# turnsig2.net
KiCad netlist of a schematic drawn in Altium Designer
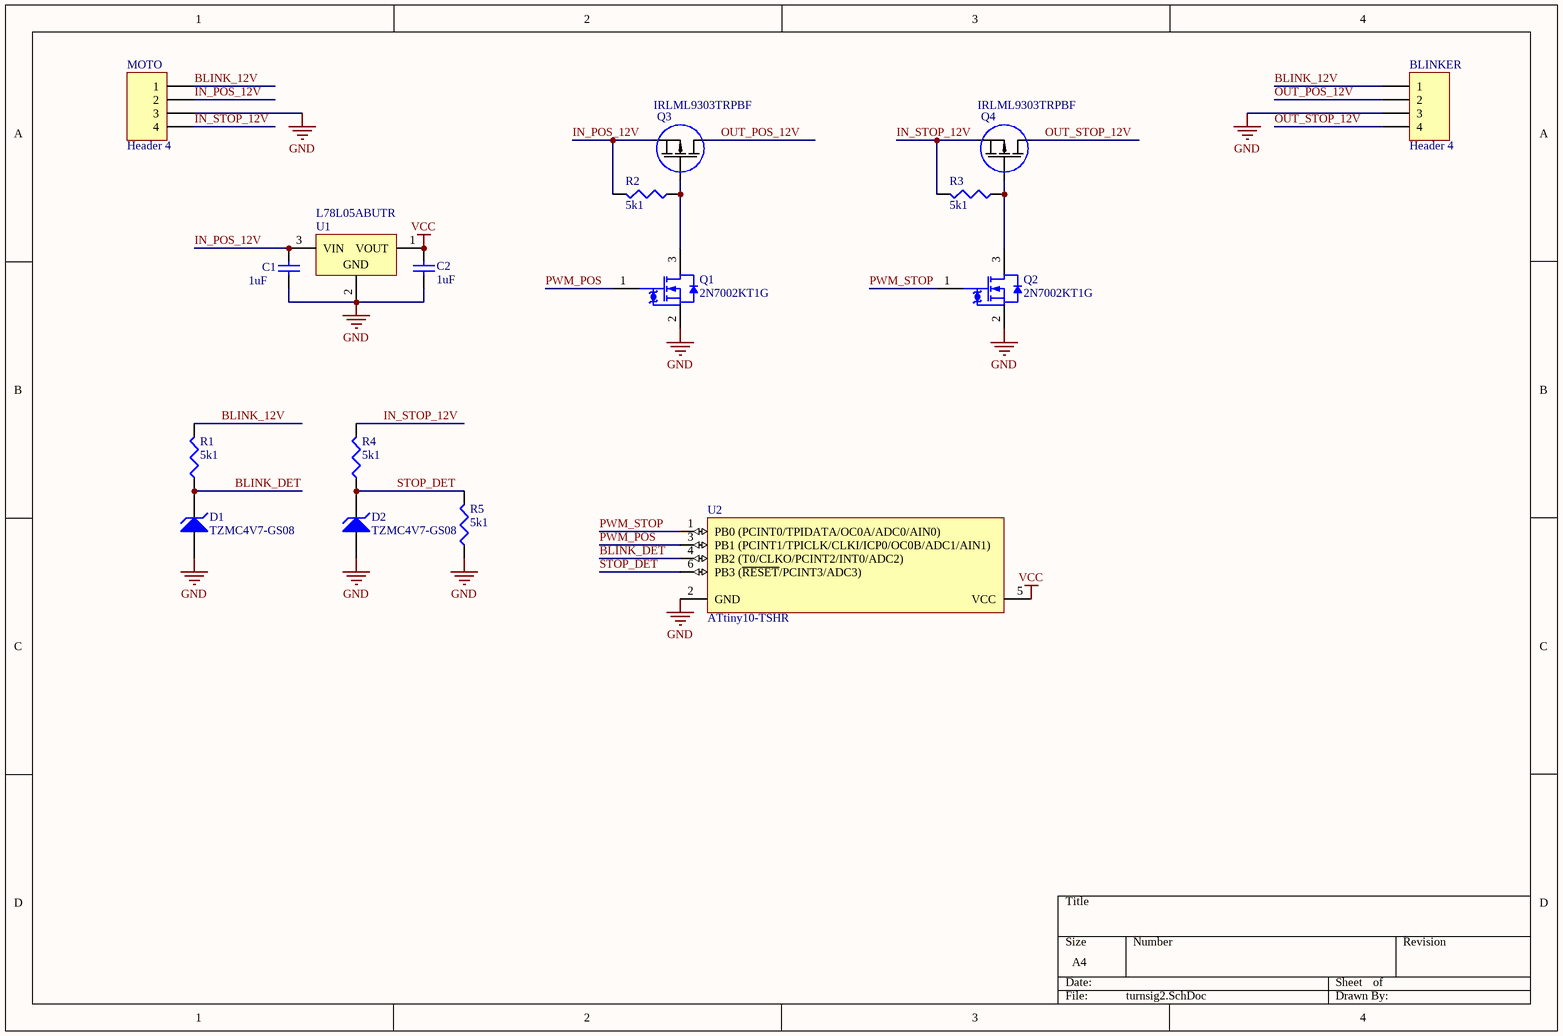
[diagram p0: turnsig2.SchDoc]

(export (version "E")
  (design (tool "Eeschema 10.0.6"))
  (components
    (comp (ref "BLINKER")
      (value "Header 4")
      (footprint "wireheader")
      (description "Header, 4-Pin")
      (fields (field (name "PUBLISHER") "Altium Limited"))
      (libsource (lib "") (part "Header 4_1"))
    )
    (comp (ref "C1")
      (value "1uF")
      (footprint "1608[0603]")
      (description "Capacitor (Semiconductor SIM Model)")
      (fields (field (name "Comment") "Cap Semi") (field (name "PUBLISHER") "Altium Limited"))
      (libsource (lib "Miscellaneous Devices") (part "Cap Semi"))
    )
    (comp (ref "C2")
      (value "1uF")
      (footprint "1608[0603]")
      (description "Capacitor (Semiconductor SIM Model)")
      (fields (field (name "Comment") "Cap Semi") (field (name "PUBLISHER") "Altium Limited"))
      (libsource (lib "Miscellaneous Devices") (part "Cap Semi"))
    )
    (comp (ref "D1")
      (value "TZMC4V7-GS08")
      (footprint "SOD-80/MLL34")
      (fields (field (name "VOLTAGE") "4V7") (field (name "PUBLISHER") "Altium Limited"))
      (libsource (lib "Miscellaneous Devices") (part "D Zener"))
    )
    (comp (ref "D2")
      (value "TZMC4V7-GS08")
      (footprint "SOD-80/MLL34")
      (fields (field (name "VOLTAGE") "4V7") (field (name "PUBLISHER") "Altium Limited"))
      (libsource (lib "Miscellaneous Devices") (part "D Zener"))
    )
    (comp (ref "MOTO")
      (value "Header 4")
      (footprint "wireheader")
      (description "Header, 4-Pin")
      (fields (field (name "PUBLISHER") "Altium Limited"))
      (libsource (lib "Miscellaneous Connectors") (part "Header 4"))
    )
    (comp (ref "Q1")
      (value "2N7002KT1G")
      (footprint "ONSC-SOT-23-3-318-08_V")
      (description "Small Signal MOSFET, 60 V, 380 mA, Single, N-Channel, 3-Pin SOT-23, Pb-Free, Tape and Reel")
      (fields (field (name "MANUFACTURER") "On Semiconductor"))
      (libsource (lib "ON Semi MOSFETs") (part "2N7002KT1G"))
    )
    (comp (ref "Q2")
      (value "2N7002KT1G")
      (footprint "ONSC-SOT-23-3-318-08_V")
      (description "Small Signal MOSFET, 60 V, 380 mA, Single, N-Channel, 3-Pin SOT-23, Pb-Free, Tape and Reel")
      (fields (field (name "MANUFACTURER") "On Semiconductor"))
      (libsource (lib "ON Semi MOSFETs") (part "2N7002KT1G"))
    )
    (comp (ref "Q3")
      (value "IRLML9303TRPBF")
      (footprint "SOT23-3N")
      (description "MOSFET-P")
      (libsource (lib "SI2323") (part "SI2323DS"))
    )
    (comp (ref "Q4")
      (value "IRLML9303TRPBF")
      (footprint "SOT23-3N")
      (description "MOSFET-P")
      (libsource (lib "SI2323") (part "SI2323DS"))
    )
    (comp (ref "R1")
      (value "5k1")
      (footprint "J1-0603")
      (description "Resistor")
      (fields (field (name "Comment") "Res3") (field (name "PUBLISHER") "Altium Limited"))
      (libsource (lib "Miscellaneous Devices") (part "Res3"))
    )
    (comp (ref "R2")
      (value "5k1")
      (footprint "J1-0603")
      (description "Resistor")
      (fields (field (name "Comment") "Res3") (field (name "PUBLISHER") "Altium Limited"))
      (libsource (lib "Miscellaneous Devices") (part "Res3"))
    )
    (comp (ref "R3")
      (value "5k1")
      (footprint "J1-0603")
      (description "Resistor")
      (fields (field (name "Comment") "Res3") (field (name "PUBLISHER") "Altium Limited"))
      (libsource (lib "Miscellaneous Devices") (part "Res3"))
    )
    (comp (ref "R4")
      (value "5k1")
      (footprint "J1-0603")
      (description "Resistor")
      (fields (field (name "Comment") "Res3") (field (name "PUBLISHER") "Altium Limited"))
      (libsource (lib "Miscellaneous Devices") (part "Res3"))
    )
    (comp (ref "R5")
      (value "5k1")
      (footprint "J1-0603")
      (description "Resistor")
      (fields (field (name "Comment") "Res3") (field (name "PUBLISHER") "Altium Limited"))
      (libsource (lib "Miscellaneous Devices") (part "Res3"))
    )
    (comp (ref "U1")
      (value "L78L05ABUTR")
      (footprint "SOT-89_N")
      (description "Positive Voltage Regulator, 5V, 4-Pin SOT-89, Tape and Reel")
      (libsource (lib "STMicroelectronics Power Management Linear Regulator") (part "L78L05ABUTR"))
    )
    (comp (ref "U2")
      (value "ATtiny10-TSHR")
      (footprint "6ST1_N")
      (fields (field (name "PUBLISHER") "Altium Limited"))
      (libsource (lib "Atmel Microcontroller 8-Bit tinyAVR") (part "ATtiny10-TSHR"))
    )
  )
  (nets
    (net (code "1") (name "/BLINK_12V") (class "Default")
      (node (ref "BLINKER") (pin "1") (pinfunction "1_1") (pintype "passive"))
      (node (ref "MOTO") (pin "1") (pinfunction "1_1") (pintype "passive"))
      (node (ref "R1") (pin "2") (pinfunction "2_2") (pintype "passive"))
    )
    (net (code "2") (name "/BLINK_DET") (class "Default")
      (node (ref "D1") (pin "2") (pinfunction "K_2") (pintype "passive"))
      (node (ref "R1") (pin "1") (pinfunction "1_1") (pintype "passive"))
      (node (ref "U2") (pin "4") (pinfunction "PB2_(T0/CLKO/PCINT2/INT0/ADC2)_4") (pintype "bidirectional"))
    )
    (net (code "3") (name "/IN_POS_12V") (class "Default")
      (node (ref "C1") (pin "1") (pinfunction "1_1") (pintype "passive"))
      (node (ref "MOTO") (pin "2") (pinfunction "2_2") (pintype "passive"))
      (node (ref "Q3") (pin "2") (pinfunction "S_2") (pintype "passive"))
      (node (ref "R2") (pin "2") (pinfunction "2_2") (pintype "passive"))
      (node (ref "U1") (pin "3") (pinfunction "VIN_3") (pintype "power_in"))
    )
    (net (code "4") (name "/IN_STOP_12V") (class "Default")
      (node (ref "MOTO") (pin "4") (pinfunction "4_4") (pintype "passive"))
      (node (ref "Q4") (pin "2") (pinfunction "S_2") (pintype "passive"))
      (node (ref "R3") (pin "2") (pinfunction "2_2") (pintype "passive"))
      (node (ref "R4") (pin "2") (pinfunction "2_2") (pintype "passive"))
    )
    (net (code "5") (name "/OUT_POS_12V") (class "Default")
      (node (ref "BLINKER") (pin "2") (pinfunction "2_2") (pintype "passive"))
      (node (ref "Q3") (pin "3") (pinfunction "D_3") (pintype "passive"))
    )
    (net (code "6") (name "/OUT_STOP_12V") (class "Default")
      (node (ref "BLINKER") (pin "4") (pinfunction "4_4") (pintype "passive"))
      (node (ref "Q4") (pin "3") (pinfunction "D_3") (pintype "passive"))
    )
    (net (code "7") (name "/PWM_POS") (class "Default")
      (node (ref "Q1") (pin "1") (pinfunction "G_1") (pintype "passive"))
      (node (ref "U2") (pin "3") (pinfunction "PB1_(PCINT1/TPICLK/CLKI/ICP0/OC0B/ADC1/AIN1)_3") (pintype "bidirectional"))
    )
    (net (code "8") (name "/PWM_STOP") (class "Default")
      (node (ref "Q2") (pin "1") (pinfunction "G_1") (pintype "passive"))
      (node (ref "U2") (pin "1") (pinfunction "PB0_(PCINT0/TPIDATA/OC0A/ADC0/AIN0)_1") (pintype "bidirectional"))
    )
    (net (code "9") (name "/STOP_DET") (class "Default")
      (node (ref "D2") (pin "2") (pinfunction "K_2") (pintype "passive"))
      (node (ref "R4") (pin "1") (pinfunction "1_1") (pintype "passive"))
      (node (ref "R5") (pin "2") (pinfunction "2_2") (pintype "passive"))
      (node (ref "U2") (pin "6") (pinfunction "PB3_(~{RESET}/PCINT3/ADC3)_6") (pintype "bidirectional"))
    )
    (net (code "10") (name "GND") (class "Default")
      (node (ref "BLINKER") (pin "3") (pinfunction "3_3") (pintype "passive"))
      (node (ref "C1") (pin "2") (pinfunction "2_2") (pintype "passive"))
      (node (ref "C2") (pin "2") (pinfunction "2_2") (pintype "passive"))
      (node (ref "D1") (pin "1") (pinfunction "A_1") (pintype "passive"))
      (node (ref "D2") (pin "1") (pinfunction "A_1") (pintype "passive"))
      (node (ref "MOTO") (pin "3") (pinfunction "3_3") (pintype "passive"))
      (node (ref "Q1") (pin "2") (pinfunction "S_2") (pintype "passive"))
      (node (ref "Q2") (pin "2") (pinfunction "S_2") (pintype "passive"))
      (node (ref "R5") (pin "1") (pinfunction "1_1") (pintype "passive"))
      (node (ref "U1") (pin "2") (pinfunction "GND_2") (pintype "power_in"))
      (node (ref "U2") (pin "2") (pinfunction "GND_2") (pintype "power_in"))
    )
    (net (code "11") (name "Net-(Q1-D)") (class "Default")
      (node (ref "Q1") (pin "3") (pinfunction "D_3") (pintype "passive"))
      (node (ref "Q3") (pin "1") (pinfunction "G_1") (pintype "passive"))
      (node (ref "R2") (pin "1") (pinfunction "1_1") (pintype "passive"))
    )
    (net (code "12") (name "Net-(Q2-D)") (class "Default")
      (node (ref "Q2") (pin "3") (pinfunction "D_3") (pintype "passive"))
      (node (ref "Q4") (pin "1") (pinfunction "G_1") (pintype "passive"))
      (node (ref "R3") (pin "1") (pinfunction "1_1") (pintype "passive"))
    )
    (net (code "13") (name "VCC") (class "Default")
      (node (ref "C2") (pin "1") (pinfunction "1_1") (pintype "passive"))
      (node (ref "U1") (pin "1") (pinfunction "VOUT_1") (pintype "power_in"))
      (node (ref "U2") (pin "5") (pinfunction "VCC_5") (pintype "power_in"))
    )
  )
)
